# connectors.net
KiCad netlist of a schematic drawn in Altium Designer
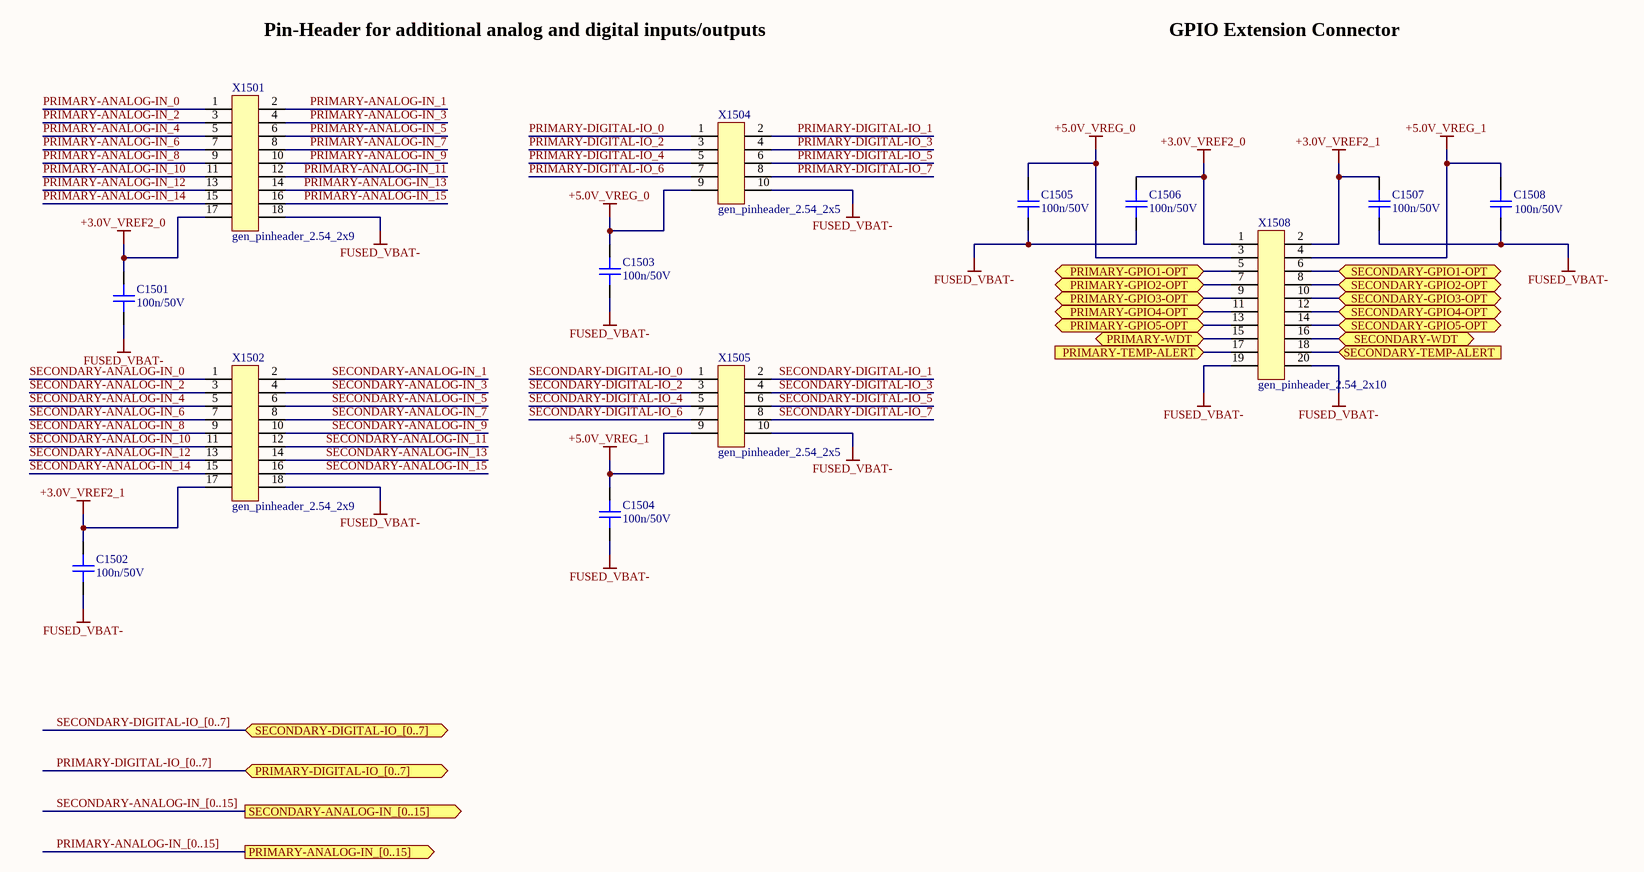
[diagram p0: connectors.SchDoc]

(export (version "E")
  (design (tool "Eeschema 10.0.6"))
  (components
    (comp (ref "C1501")
      (value "100n/50V")
      (footprint "CAPC1608X08N")
      (description "MLCC")
      (fields (field (name "PART NUMBER") "gen_C_ceramic_100n_50V_X7R_0603"))
      (libsource (lib "OE750") (part "C"))
    )
    (comp (ref "C1502")
      (value "100n/50V")
      (footprint "CAPC1608X08N")
      (description "MLCC")
      (fields (field (name "PART NUMBER") "gen_C_ceramic_100n_50V_X7R_0603"))
      (libsource (lib "OE750") (part "C"))
    )
    (comp (ref "C1503")
      (value "100n/50V")
      (footprint "CAPC1608X08N")
      (description "MLCC")
      (fields (field (name "PART NUMBER") "gen_C_ceramic_100n_50V_X7R_0603"))
      (libsource (lib "OE750") (part "C"))
    )
    (comp (ref "C1504")
      (value "100n/50V")
      (footprint "CAPC1608X08N")
      (description "MLCC")
      (fields (field (name "PART NUMBER") "gen_C_ceramic_100n_50V_X7R_0603"))
      (libsource (lib "OE750") (part "C"))
    )
    (comp (ref "C1505")
      (value "100n/50V")
      (footprint "CAPC1608X08N")
      (description "MLCC")
      (fields (field (name "PART NUMBER") "gen_C_ceramic_100n_50V_X7R_0603"))
      (libsource (lib "OE750") (part "C"))
    )
    (comp (ref "C1506")
      (value "100n/50V")
      (footprint "CAPC1608X08N")
      (description "MLCC")
      (fields (field (name "PART NUMBER") "gen_C_ceramic_100n_50V_X7R_0603"))
      (libsource (lib "OE750") (part "C"))
    )
    (comp (ref "C1507")
      (value "100n/50V")
      (footprint "CAPC1608X08N")
      (description "MLCC")
      (fields (field (name "PART NUMBER") "gen_C_ceramic_100n_50V_X7R_0603"))
      (libsource (lib "OE750") (part "C"))
    )
    (comp (ref "C1508")
      (value "100n/50V")
      (footprint "CAPC1608X08N")
      (description "MLCC")
      (fields (field (name "PART NUMBER") "gen_C_ceramic_100n_50V_X7R_0603"))
      (libsource (lib "OE750") (part "C"))
    )
    (comp (ref "X1501")
      (value "gen_pinheader_2.54_2x9")
      (footprint "Pinheader_2.54_2x9")
      (description "Standard Pinheader, THD, gerade, 2.54mm, 2-reihig")
      (libsource (lib "OE750") (part "X2x9"))
    )
    (comp (ref "X1502")
      (value "gen_pinheader_2.54_2x9")
      (footprint "Pinheader_2.54_2x9")
      (description "Standard Pinheader, THD, gerade, 2.54mm, 2-reihig")
      (libsource (lib "OE750") (part "X2x9"))
    )
    (comp (ref "X1504")
      (value "gen_pinheader_2.54_2x5")
      (footprint "Pinheader_2.54_2x5")
      (description "Standard Pinheader, THD, gerade, 2.54mm, 2-reihig")
      (libsource (lib "OE750") (part "X2x5"))
    )
    (comp (ref "X1505")
      (value "gen_pinheader_2.54_2x5")
      (footprint "Pinheader_2.54_2x5")
      (description "Standard Pinheader, THD, gerade, 2.54mm, 2-reihig")
      (libsource (lib "OE750") (part "X2x5"))
    )
    (comp (ref "X1508")
      (value "gen_pinheader_2.54_2x10")
      (footprint "Pinheader_2.54_2x10")
      (description "Standard Pinheader, THD, gerade, 2.54mm, 2-reihig")
      (libsource (lib "OE750") (part "X2x10"))
    )
  )
  (nets
    (net (code "1") (name "+3.0V_VREF2_0") (class "Default")
      (node (ref "C1501") (pin "2") (pinfunction "2_2") (pintype "passive"))
      (node (ref "C1506") (pin "2") (pinfunction "2_2") (pintype "passive"))
      (node (ref "X1501") (pin "17") (pintype "passive"))
      (node (ref "X1508") (pin "1") (pintype "passive"))
    )
    (net (code "2") (name "+3.0V_VREF2_1") (class "Default")
      (node (ref "C1502") (pin "2") (pinfunction "2_2") (pintype "passive"))
      (node (ref "C1507") (pin "2") (pinfunction "2_2") (pintype "passive"))
      (node (ref "X1502") (pin "17") (pintype "passive"))
      (node (ref "X1508") (pin "2") (pintype "passive"))
    )
    (net (code "3") (name "+5.0V_VREG_0") (class "Default")
      (node (ref "C1503") (pin "2") (pinfunction "2_2") (pintype "passive"))
      (node (ref "C1505") (pin "2") (pinfunction "2_2") (pintype "passive"))
      (node (ref "X1504") (pin "9") (pintype "passive"))
      (node (ref "X1508") (pin "3") (pintype "passive"))
    )
    (net (code "4") (name "+5.0V_VREG_1") (class "Default")
      (node (ref "C1504") (pin "2") (pinfunction "2_2") (pintype "passive"))
      (node (ref "C1508") (pin "2") (pinfunction "2_2") (pintype "passive"))
      (node (ref "X1505") (pin "9") (pintype "passive"))
      (node (ref "X1508") (pin "4") (pintype "passive"))
    )
    (net (code "5") (name "/PRIMARY-ANALOG-IN_0") (class "Default")
      (node (ref "X1501") (pin "1") (pintype "passive"))
    )
    (net (code "6") (name "/PRIMARY-ANALOG-IN_1") (class "Default")
      (node (ref "X1501") (pin "2") (pintype "passive"))
    )
    (net (code "7") (name "/PRIMARY-ANALOG-IN_2") (class "Default")
      (node (ref "X1501") (pin "3") (pintype "passive"))
    )
    (net (code "8") (name "/PRIMARY-ANALOG-IN_3") (class "Default")
      (node (ref "X1501") (pin "4") (pintype "passive"))
    )
    (net (code "9") (name "/PRIMARY-ANALOG-IN_4") (class "Default")
      (node (ref "X1501") (pin "5") (pintype "passive"))
    )
    (net (code "10") (name "/PRIMARY-ANALOG-IN_5") (class "Default")
      (node (ref "X1501") (pin "6") (pintype "passive"))
    )
    (net (code "11") (name "/PRIMARY-ANALOG-IN_6") (class "Default")
      (node (ref "X1501") (pin "7") (pintype "passive"))
    )
    (net (code "12") (name "/PRIMARY-ANALOG-IN_7") (class "Default")
      (node (ref "X1501") (pin "8") (pintype "passive"))
    )
    (net (code "13") (name "/PRIMARY-ANALOG-IN_8") (class "Default")
      (node (ref "X1501") (pin "9") (pintype "passive"))
    )
    (net (code "14") (name "/PRIMARY-ANALOG-IN_9") (class "Default")
      (node (ref "X1501") (pin "10") (pintype "passive"))
    )
    (net (code "15") (name "/PRIMARY-ANALOG-IN_10") (class "Default")
      (node (ref "X1501") (pin "11") (pintype "passive"))
    )
    (net (code "16") (name "/PRIMARY-ANALOG-IN_11") (class "Default")
      (node (ref "X1501") (pin "12") (pintype "passive"))
    )
    (net (code "17") (name "/PRIMARY-ANALOG-IN_12") (class "Default")
      (node (ref "X1501") (pin "13") (pintype "passive"))
    )
    (net (code "18") (name "/PRIMARY-ANALOG-IN_13") (class "Default")
      (node (ref "X1501") (pin "14") (pintype "passive"))
    )
    (net (code "19") (name "/PRIMARY-ANALOG-IN_14") (class "Default")
      (node (ref "X1501") (pin "15") (pintype "passive"))
    )
    (net (code "20") (name "/PRIMARY-ANALOG-IN_15") (class "Default")
      (node (ref "X1501") (pin "16") (pintype "passive"))
    )
    (net (code "22") (name "/PRIMARY-DIGITAL-IO_0") (class "Default")
      (node (ref "X1504") (pin "1") (pintype "passive"))
    )
    (net (code "23") (name "/PRIMARY-DIGITAL-IO_1") (class "Default")
      (node (ref "X1504") (pin "2") (pintype "passive"))
    )
    (net (code "24") (name "/PRIMARY-DIGITAL-IO_2") (class "Default")
      (node (ref "X1504") (pin "3") (pintype "passive"))
    )
    (net (code "25") (name "/PRIMARY-DIGITAL-IO_3") (class "Default")
      (node (ref "X1504") (pin "4") (pintype "passive"))
    )
    (net (code "26") (name "/PRIMARY-DIGITAL-IO_4") (class "Default")
      (node (ref "X1504") (pin "5") (pintype "passive"))
    )
    (net (code "27") (name "/PRIMARY-DIGITAL-IO_5") (class "Default")
      (node (ref "X1504") (pin "6") (pintype "passive"))
    )
    (net (code "28") (name "/PRIMARY-DIGITAL-IO_6") (class "Default")
      (node (ref "X1504") (pin "7") (pintype "passive"))
    )
    (net (code "29") (name "/PRIMARY-DIGITAL-IO_7") (class "Default")
      (node (ref "X1504") (pin "8") (pintype "passive"))
    )
    (net (code "31") (name "/PRIMARY-GPIO1-OPT") (class "Default")
      (node (ref "X1508") (pin "5") (pintype "passive"))
    )
    (net (code "32") (name "/PRIMARY-GPIO2-OPT") (class "Default")
      (node (ref "X1508") (pin "7") (pintype "passive"))
    )
    (net (code "33") (name "/PRIMARY-GPIO3-OPT") (class "Default")
      (node (ref "X1508") (pin "9") (pintype "passive"))
    )
    (net (code "34") (name "/PRIMARY-GPIO4-OPT") (class "Default")
      (node (ref "X1508") (pin "11") (pintype "passive"))
    )
    (net (code "35") (name "/PRIMARY-GPIO5-OPT") (class "Default")
      (node (ref "X1508") (pin "13") (pintype "passive"))
    )
    (net (code "36") (name "/PRIMARY-TEMP-ALERT") (class "Default")
      (node (ref "X1508") (pin "17") (pintype "passive"))
    )
    (net (code "37") (name "/PRIMARY-WDT") (class "Default")
      (node (ref "X1508") (pin "15") (pintype "passive"))
    )
    (net (code "38") (name "/SECONDARY-ANALOG-IN_0") (class "Default")
      (node (ref "X1502") (pin "1") (pintype "passive"))
    )
    (net (code "39") (name "/SECONDARY-ANALOG-IN_1") (class "Default")
      (node (ref "X1502") (pin "2") (pintype "passive"))
    )
    (net (code "40") (name "/SECONDARY-ANALOG-IN_2") (class "Default")
      (node (ref "X1502") (pin "3") (pintype "passive"))
    )
    (net (code "41") (name "/SECONDARY-ANALOG-IN_3") (class "Default")
      (node (ref "X1502") (pin "4") (pintype "passive"))
    )
    (net (code "42") (name "/SECONDARY-ANALOG-IN_4") (class "Default")
      (node (ref "X1502") (pin "5") (pintype "passive"))
    )
    (net (code "43") (name "/SECONDARY-ANALOG-IN_5") (class "Default")
      (node (ref "X1502") (pin "6") (pintype "passive"))
    )
    (net (code "44") (name "/SECONDARY-ANALOG-IN_6") (class "Default")
      (node (ref "X1502") (pin "7") (pintype "passive"))
    )
    (net (code "45") (name "/SECONDARY-ANALOG-IN_7") (class "Default")
      (node (ref "X1502") (pin "8") (pintype "passive"))
    )
    (net (code "46") (name "/SECONDARY-ANALOG-IN_8") (class "Default")
      (node (ref "X1502") (pin "9") (pintype "passive"))
    )
    (net (code "47") (name "/SECONDARY-ANALOG-IN_9") (class "Default")
      (node (ref "X1502") (pin "10") (pintype "passive"))
    )
    (net (code "48") (name "/SECONDARY-ANALOG-IN_10") (class "Default")
      (node (ref "X1502") (pin "11") (pintype "passive"))
    )
    (net (code "49") (name "/SECONDARY-ANALOG-IN_11") (class "Default")
      (node (ref "X1502") (pin "12") (pintype "passive"))
    )
    (net (code "50") (name "/SECONDARY-ANALOG-IN_12") (class "Default")
      (node (ref "X1502") (pin "13") (pintype "passive"))
    )
    (net (code "51") (name "/SECONDARY-ANALOG-IN_13") (class "Default")
      (node (ref "X1502") (pin "14") (pintype "passive"))
    )
    (net (code "52") (name "/SECONDARY-ANALOG-IN_14") (class "Default")
      (node (ref "X1502") (pin "15") (pintype "passive"))
    )
    (net (code "53") (name "/SECONDARY-ANALOG-IN_15") (class "Default")
      (node (ref "X1502") (pin "16") (pintype "passive"))
    )
    (net (code "55") (name "/SECONDARY-DIGITAL-IO_0") (class "Default")
      (node (ref "X1505") (pin "1") (pintype "passive"))
    )
    (net (code "56") (name "/SECONDARY-DIGITAL-IO_1") (class "Default")
      (node (ref "X1505") (pin "2") (pintype "passive"))
    )
    (net (code "57") (name "/SECONDARY-DIGITAL-IO_2") (class "Default")
      (node (ref "X1505") (pin "3") (pintype "passive"))
    )
    (net (code "58") (name "/SECONDARY-DIGITAL-IO_3") (class "Default")
      (node (ref "X1505") (pin "4") (pintype "passive"))
    )
    (net (code "59") (name "/SECONDARY-DIGITAL-IO_4") (class "Default")
      (node (ref "X1505") (pin "5") (pintype "passive"))
    )
    (net (code "60") (name "/SECONDARY-DIGITAL-IO_5") (class "Default")
      (node (ref "X1505") (pin "6") (pintype "passive"))
    )
    (net (code "61") (name "/SECONDARY-DIGITAL-IO_6") (class "Default")
      (node (ref "X1505") (pin "7") (pintype "passive"))
    )
    (net (code "62") (name "/SECONDARY-DIGITAL-IO_7") (class "Default")
      (node (ref "X1505") (pin "8") (pintype "passive"))
    )
    (net (code "64") (name "/SECONDARY-GPIO1-OPT") (class "Default")
      (node (ref "X1508") (pin "6") (pintype "passive"))
    )
    (net (code "65") (name "/SECONDARY-GPIO2-OPT") (class "Default")
      (node (ref "X1508") (pin "8") (pintype "passive"))
    )
    (net (code "66") (name "/SECONDARY-GPIO3-OPT") (class "Default")
      (node (ref "X1508") (pin "10") (pintype "passive"))
    )
    (net (code "67") (name "/SECONDARY-GPIO4-OPT") (class "Default")
      (node (ref "X1508") (pin "12") (pintype "passive"))
    )
    (net (code "68") (name "/SECONDARY-GPIO5-OPT") (class "Default")
      (node (ref "X1508") (pin "14") (pintype "passive"))
    )
    (net (code "69") (name "/SECONDARY-TEMP-ALERT") (class "Default")
      (node (ref "X1508") (pin "18") (pintype "passive"))
    )
    (net (code "70") (name "/SECONDARY-WDT") (class "Default")
      (node (ref "X1508") (pin "16") (pintype "passive"))
    )
    (net (code "71") (name "FUSED_VBAT-") (class "Default")
      (node (ref "C1501") (pin "1") (pinfunction "1_1") (pintype "passive"))
      (node (ref "C1502") (pin "1") (pinfunction "1_1") (pintype "passive"))
      (node (ref "C1503") (pin "1") (pinfunction "1_1") (pintype "passive"))
      (node (ref "C1504") (pin "1") (pinfunction "1_1") (pintype "passive"))
      (node (ref "C1505") (pin "1") (pinfunction "1_1") (pintype "passive"))
      (node (ref "C1506") (pin "1") (pinfunction "1_1") (pintype "passive"))
      (node (ref "C1507") (pin "1") (pinfunction "1_1") (pintype "passive"))
      (node (ref "C1508") (pin "1") (pinfunction "1_1") (pintype "passive"))
      (node (ref "X1501") (pin "18") (pintype "passive"))
      (node (ref "X1502") (pin "18") (pintype "passive"))
      (node (ref "X1504") (pin "10") (pintype "passive"))
      (node (ref "X1505") (pin "10") (pintype "passive"))
      (node (ref "X1508") (pin "19") (pintype "passive"))
      (node (ref "X1508") (pin "20") (pintype "passive"))
    )
  )
)
